# butt-on-mk-1_1.net
KiCad netlist of a schematic drawn in EAGLE
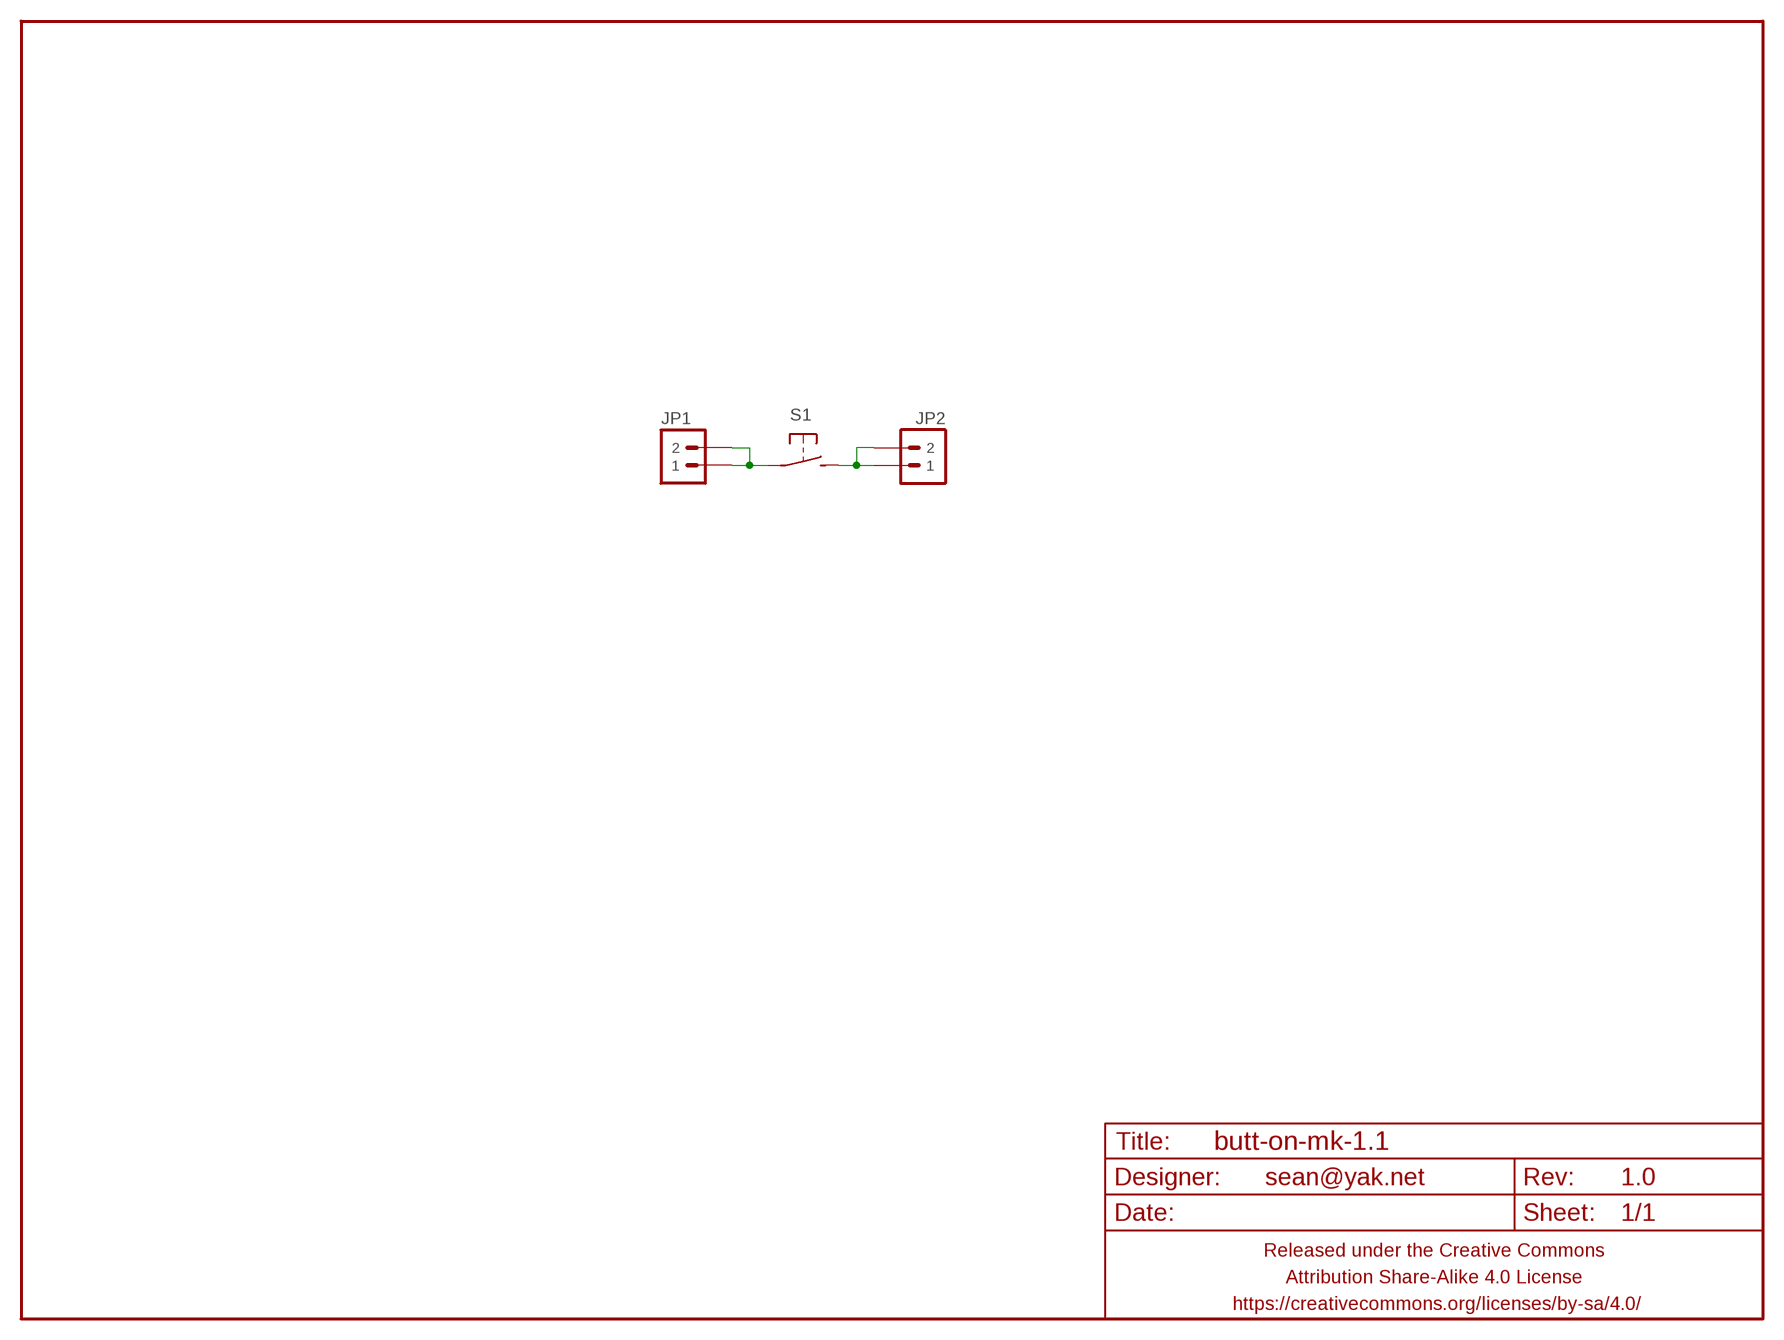
[diagram p0: schematic, sheet 1]

(export (version "E")
  (design (tool "Eeschema 10.0.6"))
  (components
    (comp (ref "FRAME1")
      (value "FRAME-LETTERNO_PACKAGE")
      (footprint "eagle-import:DUMMY")
      (fields (field (name "DESIGNER") "sean@yak.net") (field (name "VERSION") "1.0"))
      (libsource (lib "eagle-import") (part "FRAME-LETTERNO_PACKAGE"))
    )
    (comp (ref "JP1")
      (value "M02PTH-CENTERED")
      (footprint "eagle-import:1X02-CENTER")
      (libsource (lib "eagle-import") (part "M02PTH-CENTERED"))
    )
    (comp (ref "JP2")
      (value "M02PTH-CENTERED")
      (footprint "eagle-import:1X02-CENTER")
      (libsource (lib "eagle-import") (part "M02PTH-CENTERED"))
    )
    (comp (ref "S1")
      (value "SPST-NO-TACTLESS_SILK")
      (footprint "eagle-import:DTS-6-SMALL-PADS-NS")
      (libsource (lib "eagle-import") (part "SPST-NO-TACTLESS_SILK"))
    )
  )
  (nets
    (net (code "1") (name "Net-(JP1-Pad1)") (class "Default")
      (node (ref "JP1") (pin "1") (pinfunction "1_1") (pintype "passive"))
      (node (ref "JP1") (pin "2") (pinfunction "2_2") (pintype "passive"))
      (node (ref "S1") (pin "1") (pinfunction "1_1") (pintype "passive"))
      (node (ref "S1") (pin "2") (pinfunction "1_2") (pintype "passive"))
    )
    (net (code "2") (name "Net-(JP2-Pad1)") (class "Default")
      (node (ref "JP2") (pin "1") (pinfunction "1_1") (pintype "passive"))
      (node (ref "JP2") (pin "2") (pinfunction "2_2") (pintype "passive"))
      (node (ref "S1") (pin "3") (pinfunction "2_3") (pintype "passive"))
      (node (ref "S1") (pin "4") (pinfunction "2_4") (pintype "passive"))
    )
  )
)
